# microscope-light-source.net
KiCad netlist of a schematic drawn in EAGLE
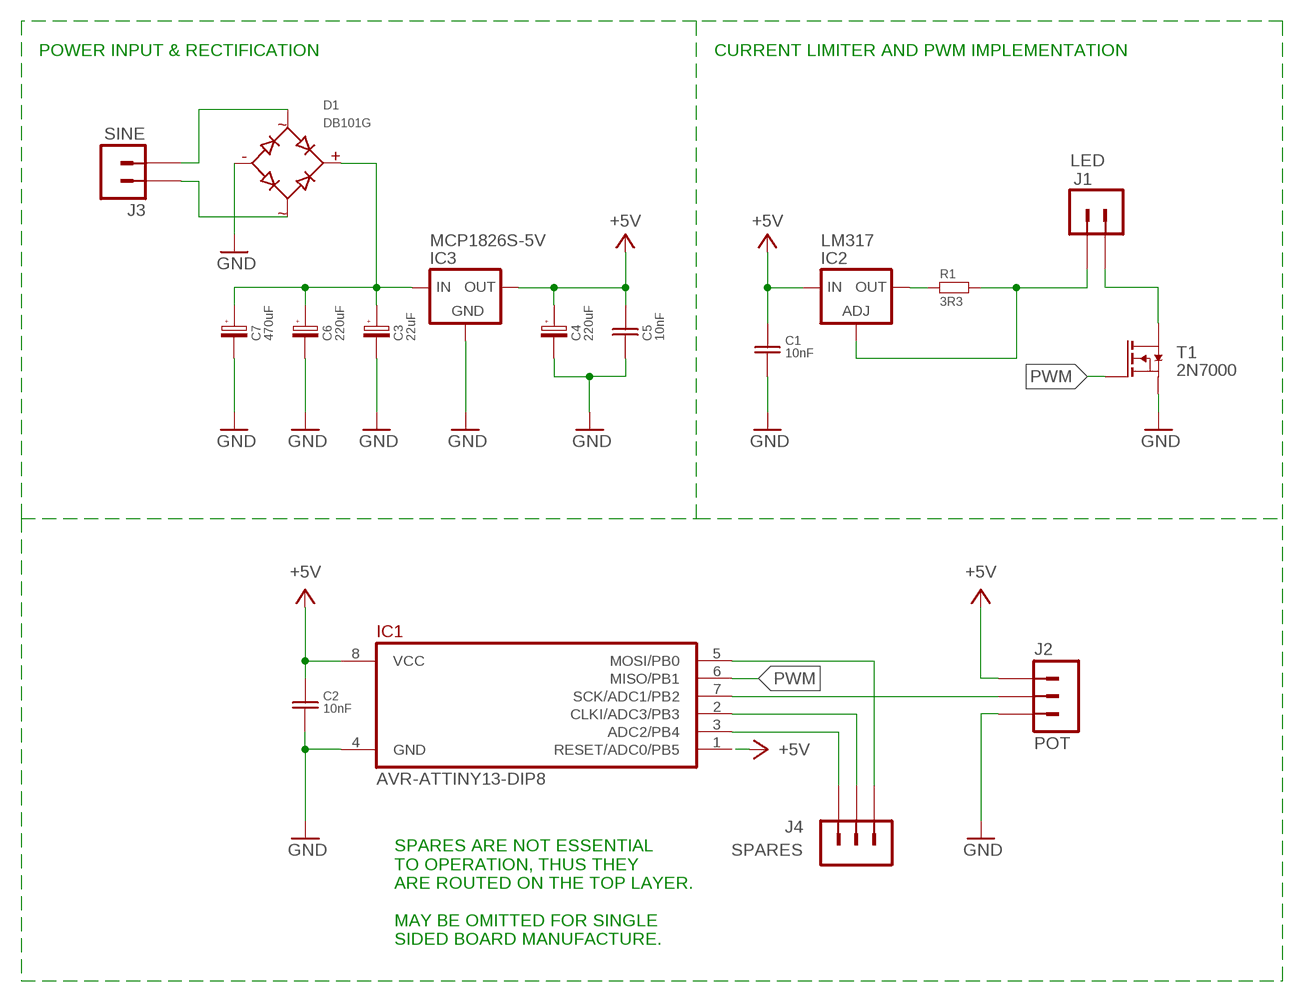
[diagram p0: schematic, sheet 1]

(export (version "E")
  (design (tool "Eeschema 10.0.6"))
  (components
    (comp (ref "C1")
      (value "10nF")
      (footprint "eagle-import:CAPACITOR-5MM-GRID")
      (libsource (lib "eagle-import") (part "CAPACITOR-TH-5MM"))
    )
    (comp (ref "C2")
      (value "10nF")
      (footprint "eagle-import:CAPACITOR-5MM-GRID")
      (libsource (lib "eagle-import") (part "CAPACITOR-TH-5MM"))
    )
    (comp (ref "C3")
      (value "22uF")
      (footprint "eagle-import:CAPACITOR-RADIAL-5MM")
      (libsource (lib "eagle-import") (part "CAPACITOR-POLARISED-TH-5MM"))
    )
    (comp (ref "C4")
      (value "220uF")
      (footprint "eagle-import:CAPACITOR-RADIAL-5MM")
      (libsource (lib "eagle-import") (part "CAPACITOR-POLARISED-TH-5MM"))
    )
    (comp (ref "C5")
      (value "10nF")
      (footprint "eagle-import:CAPACITOR-5MM-GRID")
      (libsource (lib "eagle-import") (part "CAPACITOR-TH-5MM"))
    )
    (comp (ref "C6")
      (value "220uF")
      (footprint "eagle-import:CAPACITOR-RADIAL-5MM")
      (libsource (lib "eagle-import") (part "CAPACITOR-POLARISED-TH-5MM"))
    )
    (comp (ref "C7")
      (value "470uF")
      (footprint "eagle-import:CAPACITOR-RADIAL-10MM")
      (libsource (lib "eagle-import") (part "CAPACITOR-POLARISED-TH-10MM"))
    )
    (comp (ref "D1")
      (value "DB101G")
      (footprint "eagle-import:DIL04-3-BRIDGE-RECTIFIER")
      (libsource (lib "eagle-import") (part "DIODE-BRIDGE-RECTIFIER-DB101G"))
    )
    (comp (ref "IC1")
      (value "AVR-ATTINY13-DIP8")
      (footprint "eagle-import:DIL08-3")
      (libsource (lib "eagle-import") (part "AVR-ATTINY13-DIP8"))
    )
    (comp (ref "IC2")
      (value "LM317")
      (footprint "eagle-import:TO220-HORZ-DRILL")
      (libsource (lib "eagle-import") (part "VREG-3PIN-ADJ-AOI-TO220-HORZ-DRILL"))
    )
    (comp (ref "IC3")
      (value "MCP1826S-5V")
      (footprint "eagle-import:TO220-HORZ-DRILL")
      (libsource (lib "eagle-import") (part "VREG-3PIN-IGO-TO220-HORZ-DRILL"))
    )
    (comp (ref "J1")
      (value "LED")
      (footprint "eagle-import:J02-LONG")
      (libsource (lib "eagle-import") (part "J02-LONG"))
    )
    (comp (ref "J2")
      (value "POT")
      (footprint "eagle-import:J03-LONG")
      (libsource (lib "eagle-import") (part "J03-LONG"))
    )
    (comp (ref "J3")
      (value "SINE")
      (footprint "eagle-import:J02-LONG")
      (libsource (lib "eagle-import") (part "J02-LONG"))
    )
    (comp (ref "J4")
      (value "SPARES")
      (footprint "eagle-import:J03-NOSILK")
      (libsource (lib "eagle-import") (part "J03-NOSILK"))
    )
    (comp (ref "R1")
      (value "3R3")
      (footprint "eagle-import:RESISTOR-4MMX10MM_9")
      (libsource (lib "eagle-import") (part "RESISTOR-TH-0410/9"))
    )
    (comp (ref "T1")
      (value "2N7000")
      (footprint "eagle-import:TO92-TRIANGLE")
      (libsource (lib "eagle-import") (part "MOSFET-NCHAN-SGD-TO92-TRIANGLE"))
    )
  )
  (nets
    (net (code "1") (name "+5V") (class "Default")
      (node (ref "C1") (pin "1") (pinfunction "1_1") (pintype "bidirectional"))
      (node (ref "C2") (pin "1") (pinfunction "1_1") (pintype "bidirectional"))
      (node (ref "C4") (pin "A") (pinfunction "A_A") (pintype "bidirectional"))
      (node (ref "C5") (pin "1") (pinfunction "1_1") (pintype "bidirectional"))
      (node (ref "IC1") (pin "1") (pinfunction "RESET/ADC0/PB5_1") (pintype "bidirectional"))
      (node (ref "IC1") (pin "8") (pinfunction "VCC_8") (pintype "power_in"))
      (node (ref "IC2") (pin "3") (pinfunction "IN_3") (pintype "power_in"))
      (node (ref "IC3") (pin "3") (pinfunction "OUT_3") (pintype "power_in"))
      (node (ref "J2") (pin "1") (pinfunction "1_1") (pintype "bidirectional"))
    )
    (net (code "2") (name "GND") (class "Default")
      (node (ref "C1") (pin "2") (pinfunction "2_2") (pintype "bidirectional"))
      (node (ref "C2") (pin "2") (pinfunction "2_2") (pintype "bidirectional"))
      (node (ref "C3") (pin "C") (pinfunction "C_C") (pintype "bidirectional"))
      (node (ref "C4") (pin "C") (pinfunction "C_C") (pintype "bidirectional"))
      (node (ref "C5") (pin "2") (pinfunction "2_2") (pintype "bidirectional"))
      (node (ref "C6") (pin "C") (pinfunction "C_C") (pintype "bidirectional"))
      (node (ref "C7") (pin "C") (pinfunction "C_C") (pintype "bidirectional"))
      (node (ref "D1") (pin "-") (pinfunction "-_-") (pintype "bidirectional"))
      (node (ref "IC1") (pin "4") (pinfunction "GND_4") (pintype "power_in"))
      (node (ref "IC3") (pin "2") (pinfunction "GND_2") (pintype "power_in"))
      (node (ref "J2") (pin "3") (pinfunction "3_3") (pintype "bidirectional"))
      (node (ref "T1") (pin "1") (pinfunction "SOURCE_1") (pintype "passive"))
    )
    (net (code "3") (name "Net-(D1-PadSINE0)") (class "Default")
      (node (ref "D1") (pin "SINE0") (pinfunction "SINE0_SINE0") (pintype "bidirectional"))
      (node (ref "J3") (pin "2") (pinfunction "2_2") (pintype "bidirectional"))
    )
    (net (code "4") (name "Net-(D1-PadSINE1)") (class "Default")
      (node (ref "D1") (pin "SINE1") (pinfunction "SINE1_SINE1") (pintype "bidirectional"))
      (node (ref "J3") (pin "1") (pinfunction "1_1") (pintype "bidirectional"))
    )
    (net (code "5") (name "Net-(IC1-ADC2{slash}PB4)") (class "Default")
      (node (ref "IC1") (pin "3") (pinfunction "ADC2/PB4_3") (pintype "bidirectional"))
      (node (ref "J4") (pin "3") (pinfunction "3_3") (pintype "bidirectional"))
    )
    (net (code "6") (name "Net-(IC1-CLKI{slash}ADC3{slash}PB3)") (class "Default")
      (node (ref "IC1") (pin "2") (pinfunction "CLKI/ADC3/PB3_2") (pintype "bidirectional"))
      (node (ref "J4") (pin "2") (pinfunction "2_2") (pintype "bidirectional"))
    )
    (net (code "7") (name "Net-(IC1-MOSI{slash}PB0)") (class "Default")
      (node (ref "IC1") (pin "5") (pinfunction "MOSI/PB0_5") (pintype "bidirectional"))
      (node (ref "J4") (pin "1") (pinfunction "1_1") (pintype "bidirectional"))
    )
    (net (code "8") (name "Net-(IC1-SCK{slash}ADC1{slash}PB2)") (class "Default")
      (node (ref "IC1") (pin "7") (pinfunction "SCK/ADC1/PB2_7") (pintype "bidirectional"))
      (node (ref "J2") (pin "2") (pinfunction "2_2") (pintype "bidirectional"))
    )
    (net (code "9") (name "Net-(IC2-ADJ)") (class "Default")
      (node (ref "IC2") (pin "1") (pinfunction "ADJ_1") (pintype "power_in"))
      (node (ref "J1") (pin "1") (pinfunction "1_1") (pintype "bidirectional"))
      (node (ref "R1") (pin "1") (pinfunction "1_1") (pintype "bidirectional"))
    )
    (net (code "10") (name "Net-(IC2-OUT)") (class "Default")
      (node (ref "IC2") (pin "2") (pinfunction "OUT_2") (pintype "power_in"))
      (node (ref "R1") (pin "2") (pinfunction "2_2") (pintype "bidirectional"))
    )
    (net (code "11") (name "Net-(IC3-IN)") (class "Default")
      (node (ref "C3") (pin "A") (pinfunction "A_A") (pintype "bidirectional"))
      (node (ref "C6") (pin "A") (pinfunction "A_A") (pintype "bidirectional"))
      (node (ref "C7") (pin "A") (pinfunction "A_A") (pintype "bidirectional"))
      (node (ref "D1") (pin "+") (pinfunction "+_+") (pintype "bidirectional"))
      (node (ref "IC3") (pin "1") (pinfunction "IN_1") (pintype "power_in"))
    )
    (net (code "12") (name "Net-(T1-DRAIN)") (class "Default")
      (node (ref "J1") (pin "2") (pinfunction "2_2") (pintype "bidirectional"))
      (node (ref "T1") (pin "3") (pinfunction "DRAIN_3") (pintype "passive"))
    )
    (net (code "13") (name "PWM") (class "Default")
      (node (ref "IC1") (pin "6") (pinfunction "MISO/PB1_6") (pintype "bidirectional"))
      (node (ref "T1") (pin "2") (pinfunction "GATE_2") (pintype "passive"))
    )
  )
)
